# irTxRxComponent.net
KiCad netlist of a schematic drawn in EAGLE
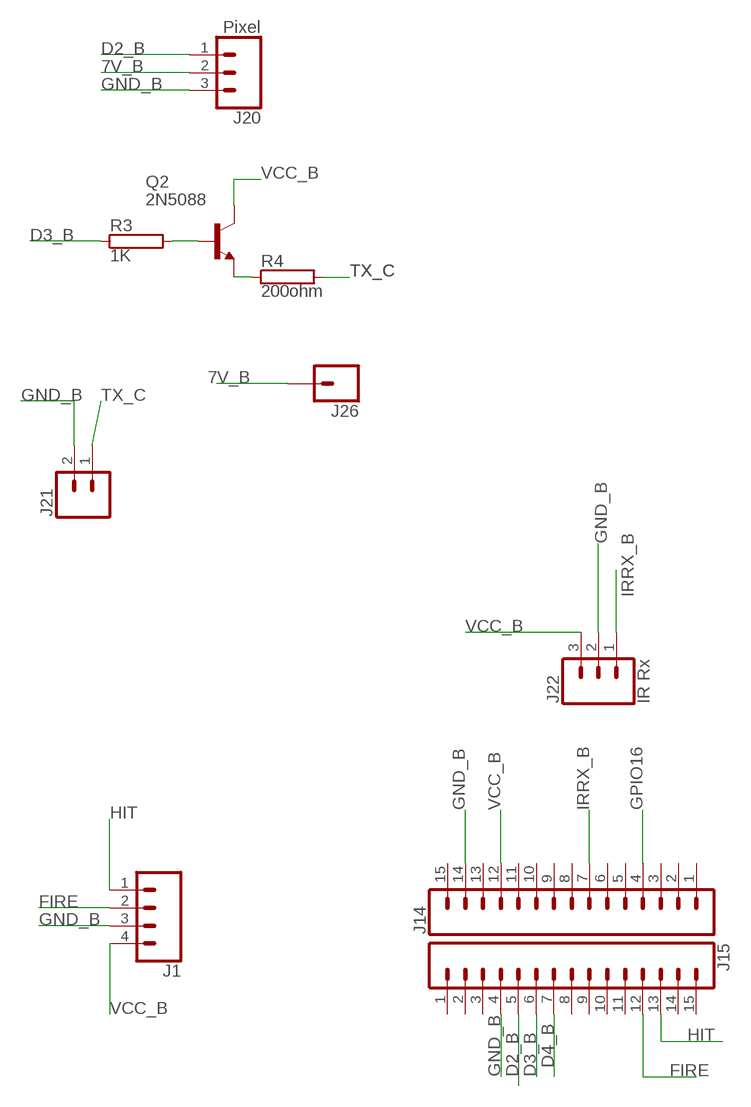
[diagram p0: schematic, sheet 1]

(export (version "E")
  (design (tool "Eeschema 10.0.6"))
  (components
    (comp (ref "J1")
      (value "CONN_04")
      (footprint "eagle-import:1X04")
      (libsource (lib "eagle-import") (part "CONN_04"))
    )
    (comp (ref "J14")
      (value "CONN_15")
      (footprint "eagle-import:1X15")
      (libsource (lib "eagle-import") (part "CONN_15"))
    )
    (comp (ref "J15")
      (value "CONN_15")
      (footprint "eagle-import:1X15")
      (libsource (lib "eagle-import") (part "CONN_15"))
    )
    (comp (ref "J20")
      (value "Pixel")
      (footprint "eagle-import:1X03")
      (libsource (lib "eagle-import") (part "CONN_03"))
    )
    (comp (ref "J21")
      (value "CONN_02")
      (footprint "eagle-import:1X02")
      (libsource (lib "eagle-import") (part "CONN_02"))
    )
    (comp (ref "J22")
      (value "IR Rx")
      (footprint "eagle-import:1X03")
      (libsource (lib "eagle-import") (part "CONN_03"))
    )
    (comp (ref "J26")
      (value "CONN_01")
      (footprint "eagle-import:1X01")
      (libsource (lib "eagle-import") (part "CONN_01"))
    )
    (comp (ref "Q2")
      (value "2N5088")
      (footprint "eagle-import:TO92")
      (libsource (lib "eagle-import") (part "2N5088"))
    )
    (comp (ref "R3")
      (value "1K")
      (footprint "eagle-import:CA0001")
      (libsource (lib "eagle-import") (part "RCA0001"))
    )
    (comp (ref "R4")
      (value "200ohm")
      (footprint "eagle-import:CA0001")
      (libsource (lib "eagle-import") (part "RCA0001"))
    )
  )
  (nets
    (net (code "1") (name "/7V_B") (class "Default")
      (node (ref "J20") (pin "2") (pinfunction "2_2") (pintype "passive"))
      (node (ref "J26") (pin "1") (pinfunction "1_1") (pintype "passive"))
    )
    (net (code "2") (name "/D2_B") (class "Default")
      (node (ref "J15") (pin "5") (pinfunction "5_5") (pintype "passive"))
      (node (ref "J20") (pin "1") (pinfunction "1_1") (pintype "passive"))
    )
    (net (code "3") (name "/D3_B") (class "Default")
      (node (ref "J15") (pin "6") (pinfunction "6_6") (pintype "passive"))
      (node (ref "R3") (pin "1") (pinfunction "1_1") (pintype "passive"))
    )
    (net (code "4") (name "/D4_B") (class "Default")
      (node (ref "J15") (pin "7") (pinfunction "7_7") (pintype "passive"))
    )
    (net (code "5") (name "/FIRE") (class "Default")
      (node (ref "J1") (pin "2") (pinfunction "2_2") (pintype "passive"))
      (node (ref "J15") (pin "12") (pinfunction "12_12") (pintype "passive"))
    )
    (net (code "6") (name "/GND_B") (class "Default")
      (node (ref "J1") (pin "3") (pinfunction "3_3") (pintype "passive"))
      (node (ref "J14") (pin "14") (pinfunction "14_14") (pintype "passive"))
      (node (ref "J15") (pin "4") (pinfunction "4_4") (pintype "passive"))
      (node (ref "J20") (pin "3") (pinfunction "3_3") (pintype "passive"))
      (node (ref "J21") (pin "2") (pinfunction "2_2") (pintype "passive"))
      (node (ref "J22") (pin "2") (pinfunction "2_2") (pintype "passive"))
    )
    (net (code "7") (name "/GPIO16") (class "Default")
      (node (ref "J14") (pin "4") (pinfunction "4_4") (pintype "passive"))
    )
    (net (code "8") (name "/HIT") (class "Default")
      (node (ref "J1") (pin "1") (pinfunction "1_1") (pintype "passive"))
      (node (ref "J15") (pin "13") (pinfunction "13_13") (pintype "passive"))
    )
    (net (code "9") (name "/IRRX_B") (class "Default")
      (node (ref "J14") (pin "7") (pinfunction "7_7") (pintype "passive"))
      (node (ref "J22") (pin "1") (pinfunction "1_1") (pintype "passive"))
    )
    (net (code "10") (name "/TX_C") (class "Default")
      (node (ref "J21") (pin "1") (pinfunction "1_1") (pintype "passive"))
      (node (ref "R4") (pin "2") (pinfunction "2_2") (pintype "passive"))
    )
    (net (code "11") (name "/VCC_B") (class "Default")
      (node (ref "J1") (pin "4") (pinfunction "4_4") (pintype "passive"))
      (node (ref "J14") (pin "12") (pinfunction "12_12") (pintype "passive"))
      (node (ref "J22") (pin "3") (pinfunction "3_3") (pintype "passive"))
      (node (ref "Q2") (pin "1") (pinfunction "C_1") (pintype "passive"))
    )
    (net (code "12") (name "Net-(Q2-B)") (class "Default")
      (node (ref "Q2") (pin "2") (pinfunction "B_2") (pintype "passive"))
      (node (ref "R3") (pin "2") (pinfunction "2_2") (pintype "passive"))
    )
    (net (code "13") (name "Net-(Q2-E)") (class "Default")
      (node (ref "Q2") (pin "3") (pinfunction "E_3") (pintype "passive"))
      (node (ref "R4") (pin "1") (pinfunction "1_1") (pintype "passive"))
    )
    (net (code "14") (name "unconnected-(J14-Pad1)") (class "Default")
      (node (ref "J14") (pin "1") (pinfunction "1_1") (pintype "passive"))
    )
    (net (code "15") (name "unconnected-(J14-Pad2)") (class "Default")
      (node (ref "J14") (pin "2") (pinfunction "2_2") (pintype "passive"))
    )
    (net (code "16") (name "unconnected-(J14-Pad3)") (class "Default")
      (node (ref "J14") (pin "3") (pinfunction "3_3") (pintype "passive"))
    )
    (net (code "17") (name "unconnected-(J14-Pad5)") (class "Default")
      (node (ref "J14") (pin "5") (pinfunction "5_5") (pintype "passive"))
    )
    (net (code "18") (name "unconnected-(J14-Pad6)") (class "Default")
      (node (ref "J14") (pin "6") (pinfunction "6_6") (pintype "passive"))
    )
    (net (code "19") (name "unconnected-(J14-Pad8)") (class "Default")
      (node (ref "J14") (pin "8") (pinfunction "8_8") (pintype "passive"))
    )
    (net (code "20") (name "unconnected-(J14-Pad9)") (class "Default")
      (node (ref "J14") (pin "9") (pinfunction "9_9") (pintype "passive"))
    )
    (net (code "21") (name "unconnected-(J14-Pad10)") (class "Default")
      (node (ref "J14") (pin "10") (pinfunction "10_10") (pintype "passive"))
    )
    (net (code "22") (name "unconnected-(J14-Pad11)") (class "Default")
      (node (ref "J14") (pin "11") (pinfunction "11_11") (pintype "passive"))
    )
    (net (code "23") (name "unconnected-(J14-Pad13)") (class "Default")
      (node (ref "J14") (pin "13") (pinfunction "13_13") (pintype "passive"))
    )
    (net (code "24") (name "unconnected-(J14-Pad15)") (class "Default")
      (node (ref "J14") (pin "15") (pinfunction "15_15") (pintype "passive"))
    )
    (net (code "25") (name "unconnected-(J15-Pad1)") (class "Default")
      (node (ref "J15") (pin "1") (pinfunction "1_1") (pintype "passive"))
    )
    (net (code "26") (name "unconnected-(J15-Pad2)") (class "Default")
      (node (ref "J15") (pin "2") (pinfunction "2_2") (pintype "passive"))
    )
    (net (code "27") (name "unconnected-(J15-Pad3)") (class "Default")
      (node (ref "J15") (pin "3") (pinfunction "3_3") (pintype "passive"))
    )
    (net (code "28") (name "unconnected-(J15-Pad8)") (class "Default")
      (node (ref "J15") (pin "8") (pinfunction "8_8") (pintype "passive"))
    )
    (net (code "29") (name "unconnected-(J15-Pad9)") (class "Default")
      (node (ref "J15") (pin "9") (pinfunction "9_9") (pintype "passive"))
    )
    (net (code "30") (name "unconnected-(J15-Pad10)") (class "Default")
      (node (ref "J15") (pin "10") (pinfunction "10_10") (pintype "passive"))
    )
    (net (code "31") (name "unconnected-(J15-Pad11)") (class "Default")
      (node (ref "J15") (pin "11") (pinfunction "11_11") (pintype "passive"))
    )
    (net (code "32") (name "unconnected-(J15-Pad14)") (class "Default")
      (node (ref "J15") (pin "14") (pinfunction "14_14") (pintype "passive"))
    )
    (net (code "33") (name "unconnected-(J15-Pad15)") (class "Default")
      (node (ref "J15") (pin "15") (pinfunction "15_15") (pintype "passive"))
    )
  )
)
